# ESP32.net
KiCad netlist of a schematic drawn in Altium Designer
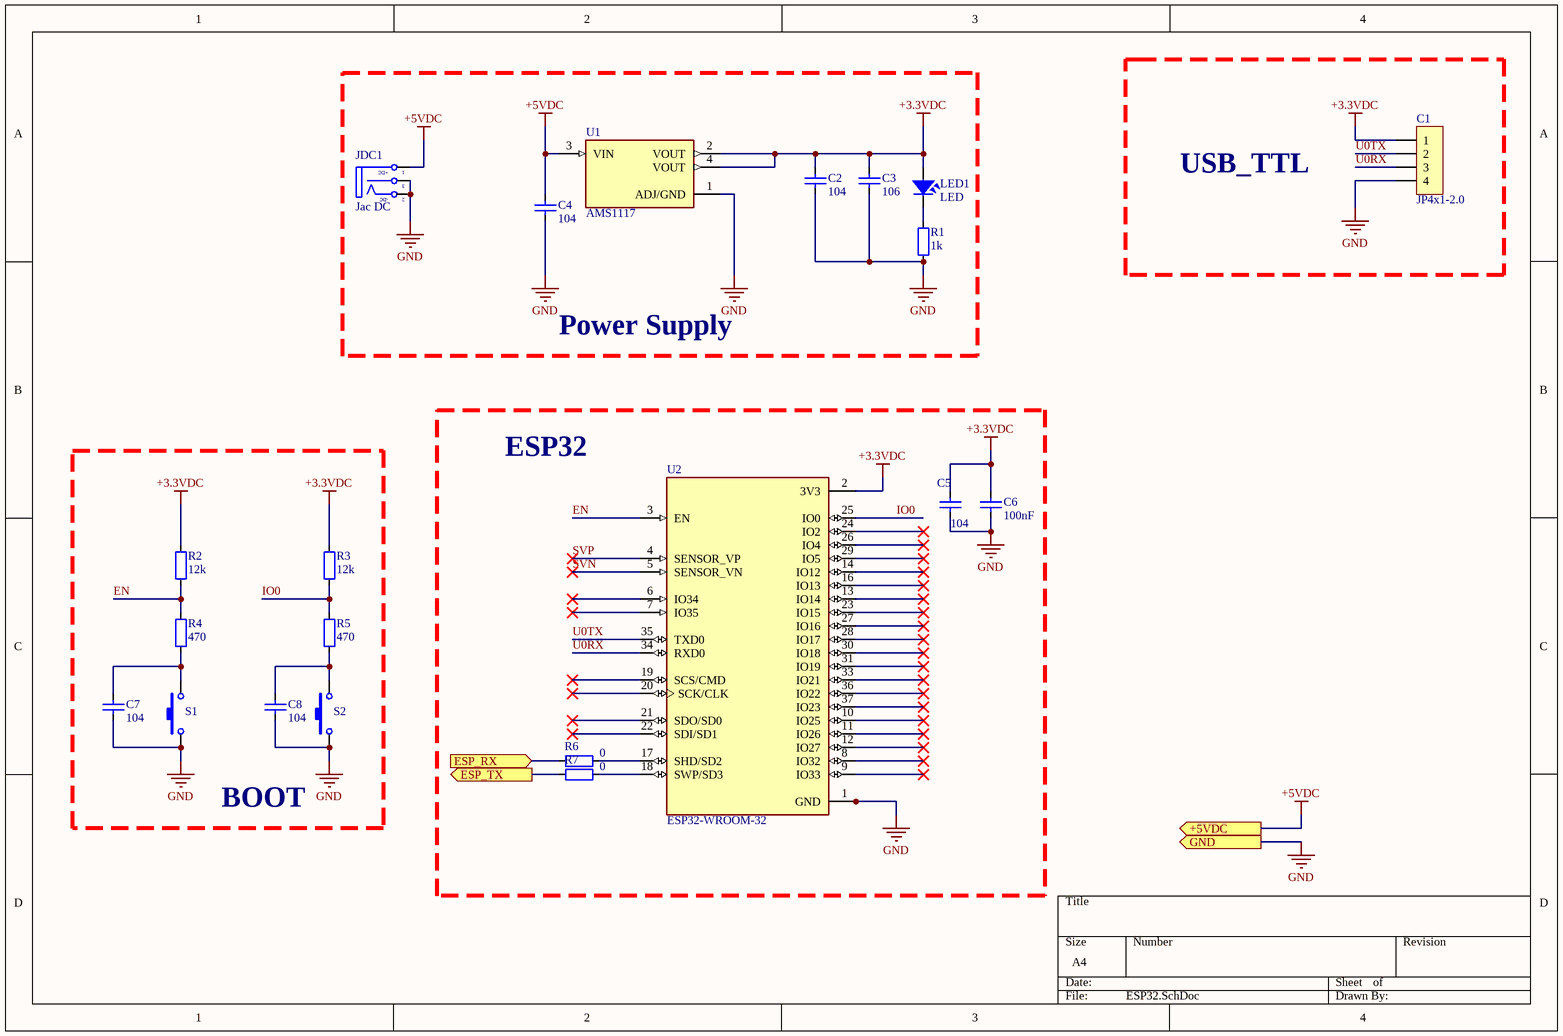
[diagram p0: ESP32.SchDoc]

(export (version "E")
  (design (tool "Eeschema 10.0.6"))
  (components
    (comp (ref "C1")
      (value "JP4x1-2.0")
      (footprint "J4-D1T")
      (description "WR-PHD 2.00 mm Socket Header")
      (fields
        (field (name "MANUFACTURER") "Würth Elektronik eiSos GmbH")
        (field (name "PARTNO") "62000411821")
        (field (name "CREATED BY") "Karrer Zheng")
      )
      (libsource (lib "My Library") (part "JP4x1-2.0"))
    )
    (comp (ref "C2")
      (value "104")
      (footprint "CAP_0805")
      (description "Capacitor")
      (fields (field (name "PUBLISHER") "Altium Limited"))
      (libsource (lib "My Library") (part "CapSMD"))
    )
    (comp (ref "C3")
      (value "106")
      (footprint "CAP_0805")
      (description "Capacitor")
      (fields (field (name "PUBLISHER") "Altium Limited"))
      (libsource (lib "My Library") (part "CapSMD"))
    )
    (comp (ref "C4")
      (value "104")
      (footprint "CAP_0805")
      (description "Capacitor")
      (fields (field (name "PUBLISHER") "Altium Limited"))
      (libsource (lib "My Library") (part "CapSMD"))
    )
    (comp (ref "C5")
      (value "104")
      (footprint "CAP_0805")
      (description "Capacitor")
      (fields (field (name "PUBLISHER") "Altium Limited"))
      (libsource (lib "My Library") (part "CapSMD"))
    )
    (comp (ref "C6")
      (value "100nF")
      (footprint "CAP_0805")
      (description "Capacitor")
      (fields (field (name "PUBLISHER") "Altium Limited"))
      (libsource (lib "My Library") (part "CapSMD"))
    )
    (comp (ref "C7")
      (value "104")
      (footprint "CAP_0805")
      (description "Capacitor")
      (fields (field (name "PUBLISHER") "Altium Limited"))
      (libsource (lib "My Library") (part "CapSMD"))
    )
    (comp (ref "C8")
      (value "104")
      (footprint "CAP_0805")
      (description "Capacitor")
      (fields (field (name "PUBLISHER") "Altium Limited"))
      (libsource (lib "My Library") (part "CapSMD"))
    )
    (comp (ref "JDC1")
      (value "Jac DC")
      (footprint "DC-IN")
      (description "Jac DC input")
      (libsource (lib "My Library") (part "DCIN"))
    )
    (comp (ref "LED1")
      (value "LED")
      (footprint "LED-0805-Red")
      (description "LED Single colour Green and Red")
      (libsource (lib "My Library") (part "LED"))
    )
    (comp (ref "R1")
      (value "1k")
      (footprint "RES-SMD-0805")
      (description "Resistor")
      (fields
        (field (name "MANUFACTURER") "Generic Components")
        (field (name "PUBLISHER") "Altium Hobart Technology Centre")
      )
      (libsource (lib "My Library") (part "Resistor - SMD"))
    )
    (comp (ref "R2")
      (value "12k")
      (footprint "RES-SMD-0805")
      (description "Resistor")
      (fields
        (field (name "MANUFACTURER") "Generic Components")
        (field (name "PUBLISHER") "Altium Hobart Technology Centre")
      )
      (libsource (lib "My Library") (part "Resistor - SMD"))
    )
    (comp (ref "R3")
      (value "12k")
      (footprint "RES-SMD-0805")
      (description "Resistor")
      (fields
        (field (name "MANUFACTURER") "Generic Components")
        (field (name "PUBLISHER") "Altium Hobart Technology Centre")
      )
      (libsource (lib "My Library") (part "Resistor - SMD"))
    )
    (comp (ref "R4")
      (value "470")
      (footprint "RES-SMD-0805")
      (description "Resistor")
      (fields
        (field (name "MANUFACTURER") "Generic Components")
        (field (name "PUBLISHER") "Altium Hobart Technology Centre")
      )
      (libsource (lib "My Library") (part "Resistor - SMD"))
    )
    (comp (ref "R5")
      (value "470")
      (footprint "RES-SMD-0805")
      (description "Resistor")
      (fields
        (field (name "MANUFACTURER") "Generic Components")
        (field (name "PUBLISHER") "Altium Hobart Technology Centre")
      )
      (libsource (lib "My Library") (part "Resistor - SMD"))
    )
    (comp (ref "R6")
      (value "0")
      (footprint "RES-SMD-0805")
      (description "Resistor")
      (fields
        (field (name "MANUFACTURER") "Generic Components")
        (field (name "PUBLISHER") "Altium Hobart Technology Centre")
      )
      (libsource (lib "My Library") (part "Resistor - SMD"))
    )
    (comp (ref "R7")
      (value "0")
      (footprint "RES-SMD-0805")
      (description "Resistor")
      (fields
        (field (name "MANUFACTURER") "Generic Components")
        (field (name "PUBLISHER") "Altium Hobart Technology Centre")
      )
      (libsource (lib "My Library") (part "Resistor - SMD"))
    )
    (comp (ref "S1")
      (value "SW-SMD")
      (footprint "SW-SMD")
      (description "Switch")
      (fields (field (name "PUBLISHER") "Altium Limited"))
      (libsource (lib "My Library") (part "SW-SMD"))
    )
    (comp (ref "S2")
      (value "SW-SMD")
      (footprint "SW-SMD")
      (description "Switch")
      (fields (field (name "PUBLISHER") "Altium Limited"))
      (libsource (lib "My Library") (part "SW-SMD"))
    )
    (comp (ref "U1")
      (value "AMS1117")
      (footprint "SOT229P700X180-4N")
      (description "1A LOW DROPOUT VOLTAGE REGULATOR SOT-223")
      (fields (field (name "MF") "Advanced Monolithic Systems"))
      (libsource (lib "AMS1117") (part "AMS1117"))
    )
    (comp (ref "U2")
      (value "ESP32-WROOM-32")
      (footprint "MODULE_ESP32-WROOM-32")
      (description "Bluetooth, WiFi Transceiver Module 2.4GHz ~ 2.5GHz Surface Mount")
      (fields (field (name "MF") "Espressif Systems") (field (name "DIGI-KEY_PART_NUMBER") "1904-1010-1-ND"))
      (libsource (lib "My Library") (part "ESP32-WROOM-32"))
    )
  )
  (nets
    (net (code "1") (name "+3.3VDC") (class "Default")
      (node (ref "C1") (pin "1") (pinfunction "1_1") (pintype "passive"))
      (node (ref "C2") (pin "2") (pinfunction "2_2") (pintype "passive"))
      (node (ref "C3") (pin "2") (pinfunction "2_2") (pintype "passive"))
      (node (ref "C5") (pin "2") (pinfunction "2_2") (pintype "passive"))
      (node (ref "C6") (pin "2") (pinfunction "2_2") (pintype "passive"))
      (node (ref "LED1") (pin "1") (pinfunction "1_1") (pintype "passive"))
      (node (ref "R2") (pin "1") (pinfunction "1_1") (pintype "passive"))
      (node (ref "R3") (pin "1") (pinfunction "1_1") (pintype "passive"))
      (node (ref "U1") (pin "2") (pinfunction "VOUT_2") (pintype "output"))
      (node (ref "U1") (pin "4") (pinfunction "VOUT_4") (pintype "output"))
      (node (ref "U2") (pin "2") (pinfunction "3V3_2") (pintype "power_in"))
    )
    (net (code "2") (name "+5VDC") (class "Default")
      (node (ref "C4") (pin "2") (pinfunction "2_2") (pintype "passive"))
      (node (ref "JDC1") (pin "1") (pinfunction "T_1") (pintype "passive"))
      (node (ref "U1") (pin "3") (pinfunction "VIN_3") (pintype "input"))
    )
    (net (code "3") (name "/EN") (class "Default")
      (node (ref "R2") (pin "2") (pinfunction "2_2") (pintype "passive"))
      (node (ref "R4") (pin "1") (pinfunction "1_1") (pintype "passive"))
      (node (ref "U2") (pin "3") (pinfunction "EN_3") (pintype "input"))
    )
    (net (code "4") (name "/ESP_RX") (class "Default")
      (node (ref "R6") (pin "1") (pinfunction "1_1") (pintype "passive"))
    )
    (net (code "5") (name "/ESP_TX") (class "Default")
      (node (ref "R7") (pin "1") (pinfunction "1_1") (pintype "passive"))
    )
    (net (code "6") (name "/IO0") (class "Default")
      (node (ref "R3") (pin "2") (pinfunction "2_2") (pintype "passive"))
      (node (ref "R5") (pin "1") (pinfunction "1_1") (pintype "passive"))
      (node (ref "U2") (pin "25") (pinfunction "IO0_25") (pintype "bidirectional"))
    )
    (net (code "7") (name "/SVN") (class "Default")
      (node (ref "U2") (pin "5") (pinfunction "SENSOR_VN_5") (pintype "input+no_connect"))
    )
    (net (code "8") (name "/SVP") (class "Default")
      (node (ref "U2") (pin "4") (pinfunction "SENSOR_VP_4") (pintype "input+no_connect"))
    )
    (net (code "9") (name "/U0RX") (class "Default")
      (node (ref "C1") (pin "3") (pinfunction "3_3") (pintype "passive"))
      (node (ref "U2") (pin "34") (pinfunction "RXD0_34") (pintype "bidirectional"))
    )
    (net (code "10") (name "/U0TX") (class "Default")
      (node (ref "C1") (pin "2") (pinfunction "2_2") (pintype "passive"))
      (node (ref "U2") (pin "35") (pinfunction "TXD0_35") (pintype "bidirectional"))
    )
    (net (code "11") (name "GND") (class "Default")
      (node (ref "C1") (pin "4") (pinfunction "4_4") (pintype "passive"))
      (node (ref "C2") (pin "1") (pinfunction "1_1") (pintype "passive"))
      (node (ref "C3") (pin "1") (pinfunction "1_1") (pintype "passive"))
      (node (ref "C4") (pin "1") (pinfunction "1_1") (pintype "passive"))
      (node (ref "C5") (pin "1") (pinfunction "1_1") (pintype "passive"))
      (node (ref "C6") (pin "1") (pinfunction "1_1") (pintype "passive"))
      (node (ref "C7") (pin "1") (pinfunction "1_1") (pintype "passive"))
      (node (ref "C8") (pin "1") (pinfunction "1_1") (pintype "passive"))
      (node (ref "JDC1") (pin "2") (pinfunction "TN_2") (pintype "passive"))
      (node (ref "JDC1") (pin "3") (pinfunction "S_3") (pintype "power_in"))
      (node (ref "R1") (pin "1") (pinfunction "1_1") (pintype "passive"))
      (node (ref "S1") (pin "1") (pinfunction "1_1") (pintype "passive"))
      (node (ref "S2") (pin "1") (pinfunction "1_1") (pintype "passive"))
      (node (ref "U1") (pin "1") (pinfunction "ADJ/GND_1") (pintype "power_in"))
      (node (ref "U2") (pin "1") (pinfunction "GND_1") (pintype "power_in"))
      (node (ref "U2") (pin "15") (pinfunction "GND_15") (pintype "power_in"))
      (node (ref "U2") (pin "38") (pinfunction "GND_38") (pintype "power_in"))
      (node (ref "U2") (pin "39_1") (pinfunction "GND_39_1") (pintype "power_in"))
      (node (ref "U2") (pin "39_10") (pinfunction "GND_39_10") (pintype "power_in"))
      (node (ref "U2") (pin "39_11") (pinfunction "GND_39_11") (pintype "power_in"))
      (node (ref "U2") (pin "39_12") (pinfunction "GND_39_12") (pintype "power_in"))
      (node (ref "U2") (pin "39_13") (pinfunction "GND_39_13") (pintype "power_in"))
      (node (ref "U2") (pin "39_14") (pinfunction "GND_39_14") (pintype "power_in"))
      (node (ref "U2") (pin "39_15") (pinfunction "GND_39_15") (pintype "power_in"))
      (node (ref "U2") (pin "39_16") (pinfunction "GND_39_16") (pintype "power_in"))
      (node (ref "U2") (pin "39_17") (pinfunction "GND_39_17") (pintype "power_in"))
      (node (ref "U2") (pin "39_18") (pinfunction "GND_39_18") (pintype "power_in"))
      (node (ref "U2") (pin "39_19") (pinfunction "GND_39_19") (pintype "power_in"))
      (node (ref "U2") (pin "39_2") (pinfunction "GND_39_2") (pintype "power_in"))
      (node (ref "U2") (pin "39_20") (pinfunction "GND_39_20") (pintype "power_in"))
      (node (ref "U2") (pin "39_21") (pinfunction "GND_39_21") (pintype "power_in"))
      (node (ref "U2") (pin "39_3") (pinfunction "GND_39_3") (pintype "power_in"))
      (node (ref "U2") (pin "39_4") (pinfunction "GND_39_4") (pintype "power_in"))
      (node (ref "U2") (pin "39_5") (pinfunction "GND_39_5") (pintype "power_in"))
      (node (ref "U2") (pin "39_6") (pinfunction "GND_39_6") (pintype "power_in"))
      (node (ref "U2") (pin "39_7") (pinfunction "GND_39_7") (pintype "power_in"))
      (node (ref "U2") (pin "39_8") (pinfunction "GND_39_8") (pintype "power_in"))
      (node (ref "U2") (pin "39_9") (pinfunction "GND_39_9") (pintype "power_in"))
    )
    (net (code "12") (name "Net-(C7-Pad2)") (class "Default")
      (node (ref "C7") (pin "2") (pinfunction "2_2") (pintype "passive"))
      (node (ref "R4") (pin "2") (pinfunction "2_2") (pintype "passive"))
      (node (ref "S1") (pin "2") (pinfunction "2_2") (pintype "passive"))
    )
    (net (code "13") (name "Net-(C8-Pad2)") (class "Default")
      (node (ref "C8") (pin "2") (pinfunction "2_2") (pintype "passive"))
      (node (ref "R5") (pin "2") (pinfunction "2_2") (pintype "passive"))
      (node (ref "S2") (pin "2") (pinfunction "2_2") (pintype "passive"))
    )
    (net (code "14") (name "Net-(LED1-Pad2)") (class "Default")
      (node (ref "LED1") (pin "2") (pinfunction "2_2") (pintype "passive"))
      (node (ref "R1") (pin "2") (pinfunction "2_2") (pintype "passive"))
    )
    (net (code "15") (name "Net-(U2-SHD{slash}SD2)") (class "Default")
      (node (ref "R6") (pin "2") (pinfunction "2_2") (pintype "passive"))
      (node (ref "U2") (pin "17") (pinfunction "SHD/SD2_17") (pintype "bidirectional"))
    )
    (net (code "16") (name "Net-(U2-SWP{slash}SD3)") (class "Default")
      (node (ref "R7") (pin "2") (pinfunction "2_2") (pintype "passive"))
      (node (ref "U2") (pin "18") (pinfunction "SWP/SD3_18") (pintype "bidirectional"))
    )
    (net (code "17") (name "unconnected-(U2-IO2-Pad24)") (class "Default")
      (node (ref "U2") (pin "24") (pinfunction "IO2_24") (pintype "bidirectional+no_connect"))
    )
    (net (code "18") (name "unconnected-(U2-IO4-Pad26)") (class "Default")
      (node (ref "U2") (pin "26") (pinfunction "IO4_26") (pintype "bidirectional+no_connect"))
    )
    (net (code "19") (name "unconnected-(U2-IO5-Pad29)") (class "Default")
      (node (ref "U2") (pin "29") (pinfunction "IO5_29") (pintype "bidirectional+no_connect"))
    )
    (net (code "20") (name "unconnected-(U2-IO12-Pad14)") (class "Default")
      (node (ref "U2") (pin "14") (pinfunction "IO12_14") (pintype "bidirectional+no_connect"))
    )
    (net (code "21") (name "unconnected-(U2-IO13-Pad16)") (class "Default")
      (node (ref "U2") (pin "16") (pinfunction "IO13_16") (pintype "bidirectional+no_connect"))
    )
    (net (code "22") (name "unconnected-(U2-IO14-Pad13)") (class "Default")
      (node (ref "U2") (pin "13") (pinfunction "IO14_13") (pintype "bidirectional+no_connect"))
    )
    (net (code "23") (name "unconnected-(U2-IO15-Pad23)") (class "Default")
      (node (ref "U2") (pin "23") (pinfunction "IO15_23") (pintype "bidirectional+no_connect"))
    )
    (net (code "24") (name "unconnected-(U2-IO16-Pad27)") (class "Default")
      (node (ref "U2") (pin "27") (pinfunction "IO16_27") (pintype "bidirectional+no_connect"))
    )
    (net (code "25") (name "unconnected-(U2-IO17-Pad28)") (class "Default")
      (node (ref "U2") (pin "28") (pinfunction "IO17_28") (pintype "bidirectional+no_connect"))
    )
    (net (code "26") (name "unconnected-(U2-IO18-Pad30)") (class "Default")
      (node (ref "U2") (pin "30") (pinfunction "IO18_30") (pintype "bidirectional+no_connect"))
    )
    (net (code "27") (name "unconnected-(U2-IO19-Pad31)") (class "Default")
      (node (ref "U2") (pin "31") (pinfunction "IO19_31") (pintype "bidirectional+no_connect"))
    )
    (net (code "28") (name "unconnected-(U2-IO21-Pad33)") (class "Default")
      (node (ref "U2") (pin "33") (pinfunction "IO21_33") (pintype "bidirectional+no_connect"))
    )
    (net (code "29") (name "unconnected-(U2-IO22-Pad36)") (class "Default")
      (node (ref "U2") (pin "36") (pinfunction "IO22_36") (pintype "bidirectional+no_connect"))
    )
    (net (code "30") (name "unconnected-(U2-IO23-Pad37)") (class "Default")
      (node (ref "U2") (pin "37") (pinfunction "IO23_37") (pintype "bidirectional+no_connect"))
    )
    (net (code "31") (name "unconnected-(U2-IO25-Pad10)") (class "Default")
      (node (ref "U2") (pin "10") (pinfunction "IO25_10") (pintype "bidirectional+no_connect"))
    )
    (net (code "32") (name "unconnected-(U2-IO26-Pad11)") (class "Default")
      (node (ref "U2") (pin "11") (pinfunction "IO26_11") (pintype "bidirectional+no_connect"))
    )
    (net (code "33") (name "unconnected-(U2-IO27-Pad12)") (class "Default")
      (node (ref "U2") (pin "12") (pinfunction "IO27_12") (pintype "bidirectional+no_connect"))
    )
    (net (code "34") (name "unconnected-(U2-IO32-Pad8)") (class "Default")
      (node (ref "U2") (pin "8") (pinfunction "IO32_8") (pintype "bidirectional+no_connect"))
    )
    (net (code "35") (name "unconnected-(U2-IO33-Pad9)") (class "Default")
      (node (ref "U2") (pin "9") (pinfunction "IO33_9") (pintype "bidirectional+no_connect"))
    )
    (net (code "36") (name "unconnected-(U2-IO34-Pad6)") (class "Default")
      (node (ref "U2") (pin "6") (pinfunction "IO34_6") (pintype "input+no_connect"))
    )
    (net (code "37") (name "unconnected-(U2-IO35-Pad7)") (class "Default")
      (node (ref "U2") (pin "7") (pinfunction "IO35_7") (pintype "input+no_connect"))
    )
    (net (code "38") (name "unconnected-(U2-SCK{slash}CLK-Pad20)") (class "Default")
      (node (ref "U2") (pin "20") (pinfunction "SCK/CLK_20") (pintype "bidirectional+no_connect"))
    )
    (net (code "39") (name "unconnected-(U2-SCS{slash}CMD-Pad19)") (class "Default")
      (node (ref "U2") (pin "19") (pinfunction "SCS/CMD_19") (pintype "bidirectional+no_connect"))
    )
    (net (code "40") (name "unconnected-(U2-SDI{slash}SD1-Pad22)") (class "Default")
      (node (ref "U2") (pin "22") (pinfunction "SDI/SD1_22") (pintype "bidirectional+no_connect"))
    )
    (net (code "41") (name "unconnected-(U2-SDO{slash}SD0-Pad21)") (class "Default")
      (node (ref "U2") (pin "21") (pinfunction "SDO/SD0_21") (pintype "bidirectional+no_connect"))
    )
  )
)
